# Tracksoar.net
KiCad netlist of a schematic drawn in EAGLE
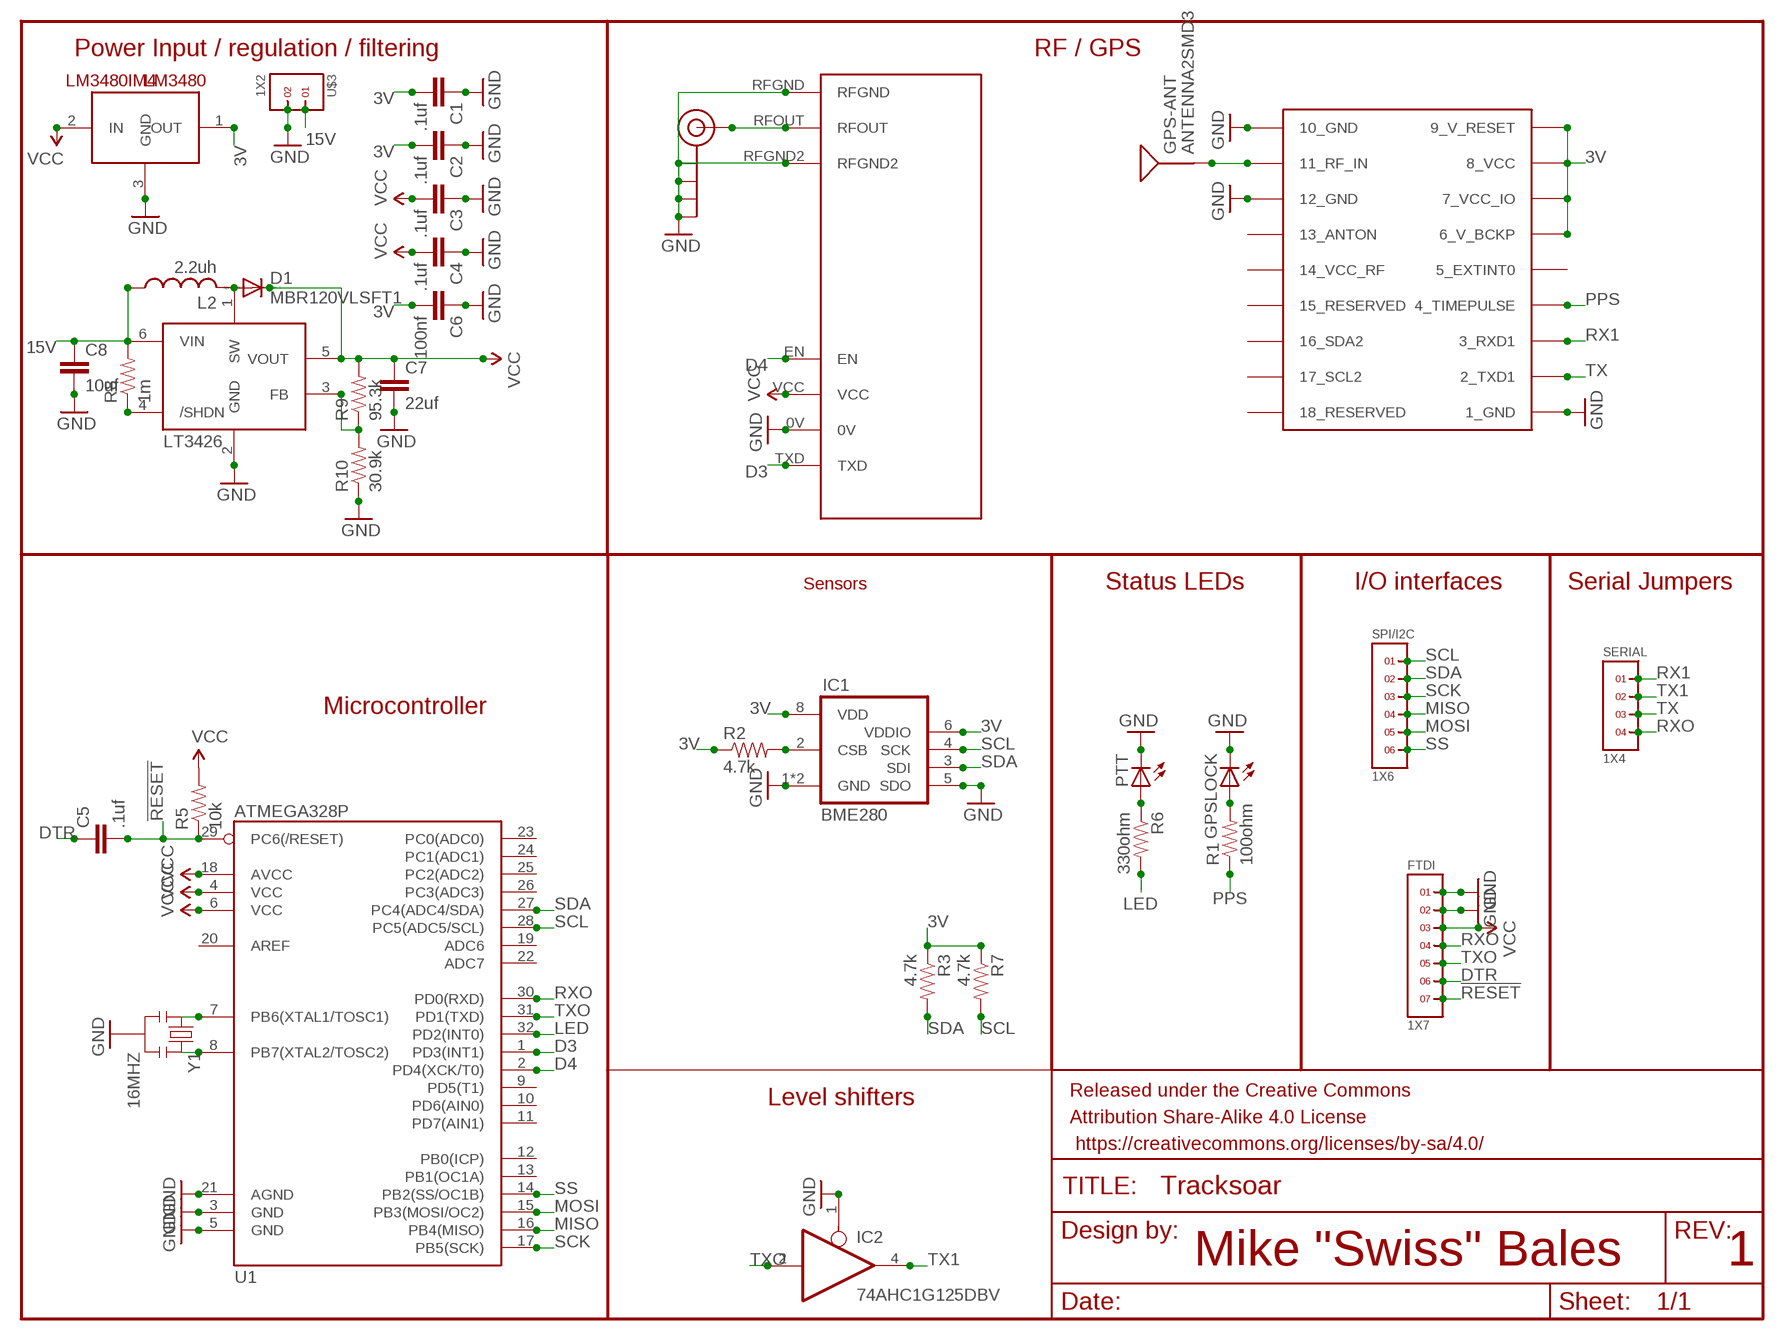
[diagram p0: schematic, sheet 1]

(export (version "E")
  (design (tool "Eeschema 10.0.6"))
  (components
    (comp (ref "C1")
      (value ".1uf")
      (footprint "eagle-import:0805")
      (libsource (lib "eagle-import") (part "CAP0805"))
    )
    (comp (ref "C2")
      (value ".1uf")
      (footprint "eagle-import:0805")
      (libsource (lib "eagle-import") (part "CAP0805"))
    )
    (comp (ref "C3")
      (value ".1uf")
      (footprint "eagle-import:0805")
      (libsource (lib "eagle-import") (part "CAP0805"))
    )
    (comp (ref "C4")
      (value ".1uf")
      (footprint "eagle-import:0805")
      (libsource (lib "eagle-import") (part "CAP0805"))
    )
    (comp (ref "C5")
      (value ".1uf")
      (footprint "eagle-import:0805")
      (libsource (lib "eagle-import") (part "CAP0805"))
    )
    (comp (ref "C6")
      (value "100nf")
      (footprint "eagle-import:0805")
      (libsource (lib "eagle-import") (part "CAP0805"))
    )
    (comp (ref "C7")
      (value "22uf")
      (footprint "eagle-import:0805")
      (libsource (lib "eagle-import") (part "CAP0805"))
    )
    (comp (ref "C8")
      (value "10uf")
      (footprint "eagle-import:0805")
      (libsource (lib "eagle-import") (part "CAP0805"))
    )
    (comp (ref "D1")
      (value "MBR120VLSFT1")
      (footprint "eagle-import:SOD123")
      (libsource (lib "eagle-import") (part "DIODE-SOD123"))
    )
    (comp (ref "FRAME1")
      (value "FRAME-LETTER")
      (footprint "eagle-import:CREATIVE_COMMONS")
      (libsource (lib "eagle-import") (part "FRAME-LETTER"))
    )
    (comp (ref "FTDI")
      (value "1X7")
      (footprint "eagle-import:1X7")
      (libsource (lib "eagle-import") (part "1X7"))
    )
    (comp (ref "GPS-ANT")
      (value "ANTENNA2SMD3")
      (footprint "eagle-import:ANTENNA-CHIP4")
      (libsource (lib "eagle-import") (part "ANTENNA2SMD3"))
    )
    (comp (ref "GPSLOCK")
      (value "LEDCHIP-LED0805")
      (footprint "eagle-import:CHIP-LED0805")
      (libsource (lib "eagle-import") (part "LEDCHIP-LED0805"))
    )
    (comp (ref "IC1")
      (value "BME280")
      (footprint "eagle-import:BME280")
      (libsource (lib "eagle-import") (part "BME280"))
    )
    (comp (ref "IC2")
      (value "74AHC1G125DBV")
      (footprint "eagle-import:SOT23-5")
      (libsource (lib "eagle-import") (part "741G125DBVAHC"))
    )
    (comp (ref "J$1")
      (value "SMA_EDGE")
      (footprint "eagle-import:SMA-EDGE")
      (libsource (lib "eagle-import") (part "SMA_EDGE"))
    )
    (comp (ref "L2")
      (value "2.2uh")
      (footprint "eagle-import:L1812")
      (libsource (lib "eagle-import") (part "L-USL1812"))
    )
    (comp (ref "LM3480")
      (value "LM3480IM4")
      (footprint "eagle-import:SOT23-3")
      (libsource (lib "eagle-import") (part "LM3480IM4"))
    )
    (comp (ref "LT3426")
      (value "LT3426")
      (footprint "eagle-import:SOT23-6")
      (libsource (lib "eagle-import") (part "LT3426"))
    )
    (comp (ref "PTT")
      (value "LEDCHIP-LED0805")
      (footprint "eagle-import:CHIP-LED0805")
      (libsource (lib "eagle-import") (part "LEDCHIP-LED0805"))
    )
    (comp (ref "R1")
      (value "100ohm")
      (footprint "eagle-import:0805")
      (libsource (lib "eagle-import") (part "RESISTOR0805-RES"))
    )
    (comp (ref "R2")
      (value "4.7k")
      (footprint "eagle-import:0805")
      (libsource (lib "eagle-import") (part "RESISTOR0805-RES"))
    )
    (comp (ref "R3")
      (value "4.7k")
      (footprint "eagle-import:0805")
      (libsource (lib "eagle-import") (part "RESISTOR0805-RES"))
    )
    (comp (ref "R5")
      (value "10k")
      (footprint "eagle-import:0805")
      (libsource (lib "eagle-import") (part "RESISTOR0805-RES"))
    )
    (comp (ref "R6")
      (value "330ohm")
      (footprint "eagle-import:0805")
      (libsource (lib "eagle-import") (part "RESISTOR0805-RES"))
    )
    (comp (ref "R7")
      (value "4.7k")
      (footprint "eagle-import:0805")
      (libsource (lib "eagle-import") (part "RESISTOR0805-RES"))
    )
    (comp (ref "R8")
      (value "1m")
      (footprint "eagle-import:0805")
      (libsource (lib "eagle-import") (part "RESISTOR0805-RES"))
    )
    (comp (ref "R9")
      (value "95.3k")
      (footprint "eagle-import:0805")
      (libsource (lib "eagle-import") (part "RESISTOR0805-RES"))
    )
    (comp (ref "R10")
      (value "30.9k")
      (footprint "eagle-import:0805")
      (libsource (lib "eagle-import") (part "RESISTOR0805-RES"))
    )
    (comp (ref "SERIAL")
      (value "1X4")
      (footprint "eagle-import:1X4")
      (libsource (lib "eagle-import") (part "1X4"))
    )
    (comp (ref "SPI/I2C")
      (value "1X6")
      (footprint "eagle-import:1X6")
      (libsource (lib "eagle-import") (part "1X6"))
    )
    (comp (ref "U$1")
      (value "UBLOX_MAX")
      (footprint "eagle-import:UBLOX_MAX")
      (libsource (lib "eagle-import") (part "UBLOX_MAX"))
    )
    (comp (ref "U$2")
      (value "RADIOMETRIX-HX1")
      (footprint "eagle-import:RADIOMETRIX-HX1")
      (libsource (lib "eagle-import") (part "RADIOMETRIX-HX1"))
    )
    (comp (ref "U$3")
      (value "1X2")
      (footprint "eagle-import:1X2")
      (libsource (lib "eagle-import") (part "1X2"))
    )
    (comp (ref "U1")
      (value "ATMEGA328P")
      (footprint "eagle-import:MLF32")
      (libsource (lib "eagle-import") (part "ATMEGA168MLF"))
    )
    (comp (ref "Y1")
      (value "16MHZ")
      (footprint "eagle-import:RESONATOR-SMD")
      (libsource (lib "eagle-import") (part "RESONATOR16MHZ"))
    )
  )
  (nets
    (net (code "1") (name "/3V") (class "Default")
      (node (ref "C1") (pin "2") (pinfunction "2_2") (pintype "passive"))
      (node (ref "C2") (pin "2") (pinfunction "2_2") (pintype "passive"))
      (node (ref "C6") (pin "2") (pinfunction "2_2") (pintype "passive"))
      (node (ref "IC1") (pin "6") (pinfunction "VDDIO_6") (pintype "power_in"))
      (node (ref "IC1") (pin "8") (pinfunction "VDD_8") (pintype "power_in"))
      (node (ref "LM3480") (pin "1") (pinfunction "OUT_1") (pintype "bidirectional"))
      (node (ref "R2") (pin "1") (pinfunction "1_1") (pintype "passive"))
      (node (ref "R3") (pin "1") (pinfunction "1_1") (pintype "passive"))
      (node (ref "R7") (pin "1") (pinfunction "1_1") (pintype "passive"))
      (node (ref "U$1") (pin "6_V_BCKP") (pinfunction "6_V_BCKP_6_V_BCKP") (pintype "bidirectional"))
      (node (ref "U$1") (pin "7_VCC_IO") (pinfunction "7_VCC_IO_7_VCC_IO") (pintype "power_in"))
      (node (ref "U$1") (pin "8_VCC") (pinfunction "8_VCC_8_VCC") (pintype "power_in"))
      (node (ref "U$1") (pin "9_V_RESET") (pinfunction "9_V_RESET_9_V_RESET") (pintype "power_in"))
    )
    (net (code "2") (name "/15V") (class "Default")
      (node (ref "C8") (pin "1") (pinfunction "1_1") (pintype "passive"))
      (node (ref "L2") (pin "1") (pinfunction "1_1") (pintype "passive"))
      (node (ref "LT3426") (pin "6") (pinfunction "VIN_6") (pintype "input"))
      (node (ref "R8") (pin "2") (pinfunction "2_2") (pintype "passive"))
      (node (ref "U$3") (pin "1") (pinfunction "1_1") (pintype "bidirectional"))
    )
    (net (code "3") (name "/D3") (class "Default")
      (node (ref "U$2") (pin "TXD") (pinfunction "TXD_TXD") (pintype "bidirectional"))
      (node (ref "U1") (pin "1") (pinfunction "PD3(INT1)_1") (pintype "bidirectional"))
    )
    (net (code "4") (name "/D4") (class "Default")
      (node (ref "U$2") (pin "EN") (pinfunction "EN_EN") (pintype "bidirectional"))
      (node (ref "U1") (pin "2") (pinfunction "PD4(XCK/T0)_2") (pintype "bidirectional"))
    )
    (net (code "5") (name "/DTR") (class "Default")
      (node (ref "C5") (pin "1") (pinfunction "1_1") (pintype "passive"))
      (node (ref "FTDI") (pin "6") (pinfunction "6_6") (pintype "bidirectional"))
    )
    (net (code "6") (name "/LED") (class "Default")
      (node (ref "R6") (pin "2") (pinfunction "2_2") (pintype "passive"))
      (node (ref "U1") (pin "32") (pinfunction "PD2(INT0)_32") (pintype "bidirectional"))
    )
    (net (code "7") (name "/MISO") (class "Default")
      (node (ref "SPI/I2C") (pin "4") (pinfunction "4_4") (pintype "bidirectional"))
      (node (ref "U1") (pin "16") (pinfunction "PB4(MISO)_16") (pintype "bidirectional"))
    )
    (net (code "8") (name "/MOSI") (class "Default")
      (node (ref "SPI/I2C") (pin "5") (pinfunction "5_5") (pintype "bidirectional"))
      (node (ref "U1") (pin "15") (pinfunction "PB3(MOSI/OC2)_15") (pintype "bidirectional"))
    )
    (net (code "9") (name "/PPS") (class "Default")
      (node (ref "R1") (pin "1") (pinfunction "1_1") (pintype "passive"))
      (node (ref "U$1") (pin "4_TIMEPULSE") (pinfunction "4_TIMEPULSE_4_TIMEPULSE") (pintype "bidirectional"))
    )
    (net (code "10") (name "/RX1") (class "Default")
      (node (ref "SERIAL") (pin "1") (pinfunction "1_1") (pintype "bidirectional"))
      (node (ref "U$1") (pin "3_RXD1") (pinfunction "3_RXD1_3_RXD1") (pintype "bidirectional"))
    )
    (net (code "11") (name "/RXO") (class "Default")
      (node (ref "FTDI") (pin "4") (pinfunction "4_4") (pintype "bidirectional"))
      (node (ref "SERIAL") (pin "4") (pinfunction "4_4") (pintype "bidirectional"))
      (node (ref "U1") (pin "30") (pinfunction "PD0(RXD)_30") (pintype "bidirectional"))
    )
    (net (code "12") (name "/SCK") (class "Default")
      (node (ref "SPI/I2C") (pin "3") (pinfunction "3_3") (pintype "bidirectional"))
      (node (ref "U1") (pin "17") (pinfunction "PB5(SCK)_17") (pintype "bidirectional"))
    )
    (net (code "13") (name "/SCL") (class "Default")
      (node (ref "IC1") (pin "4") (pinfunction "SCK_4") (pintype "bidirectional"))
      (node (ref "R7") (pin "2") (pinfunction "2_2") (pintype "passive"))
      (node (ref "SPI/I2C") (pin "1") (pinfunction "1_1") (pintype "bidirectional"))
      (node (ref "U1") (pin "28") (pinfunction "PC5(ADC5/SCL)_28") (pintype "bidirectional"))
    )
    (net (code "14") (name "/SDA") (class "Default")
      (node (ref "IC1") (pin "3") (pinfunction "SDI_3") (pintype "bidirectional"))
      (node (ref "R3") (pin "2") (pinfunction "2_2") (pintype "passive"))
      (node (ref "SPI/I2C") (pin "2") (pinfunction "2_2") (pintype "bidirectional"))
      (node (ref "U1") (pin "27") (pinfunction "PC4(ADC4/SDA)_27") (pintype "bidirectional"))
    )
    (net (code "15") (name "/SS") (class "Default")
      (node (ref "SPI/I2C") (pin "6") (pinfunction "6_6") (pintype "bidirectional"))
      (node (ref "U1") (pin "14") (pinfunction "PB2(SS/OC1B)_14") (pintype "bidirectional"))
    )
    (net (code "16") (name "/TX") (class "Default")
      (node (ref "SERIAL") (pin "3") (pinfunction "3_3") (pintype "bidirectional"))
      (node (ref "U$1") (pin "2_TXD1") (pinfunction "2_TXD1_2_TXD1") (pintype "bidirectional"))
    )
    (net (code "17") (name "/TX1") (class "Default")
      (node (ref "IC2") (pin "4") (pinfunction "O_4") (pintype "tri_state"))
      (node (ref "SERIAL") (pin "2") (pinfunction "2_2") (pintype "bidirectional"))
    )
    (net (code "18") (name "/TXO") (class "Default")
      (node (ref "FTDI") (pin "5") (pinfunction "5_5") (pintype "bidirectional"))
      (node (ref "IC2") (pin "2") (pinfunction "I_2") (pintype "input"))
      (node (ref "U1") (pin "31") (pinfunction "PD1(TXD)_31") (pintype "bidirectional"))
    )
    (net (code "19") (name "/~{RESET}") (class "Default")
      (node (ref "C5") (pin "2") (pinfunction "2_2") (pintype "passive"))
      (node (ref "FTDI") (pin "7") (pinfunction "7_7") (pintype "bidirectional"))
      (node (ref "R5") (pin "1") (pinfunction "1_1") (pintype "passive"))
      (node (ref "U1") (pin "29") (pinfunction "PC6(/RESET)_29") (pintype "bidirectional"))
    )
    (net (code "20") (name "GND") (class "Default")
      (node (ref "C1") (pin "1") (pinfunction "1_1") (pintype "passive"))
      (node (ref "C2") (pin "1") (pinfunction "1_1") (pintype "passive"))
      (node (ref "C3") (pin "1") (pinfunction "1_1") (pintype "passive"))
      (node (ref "C4") (pin "1") (pinfunction "1_1") (pintype "passive"))
      (node (ref "C6") (pin "1") (pinfunction "1_1") (pintype "passive"))
      (node (ref "C7") (pin "2") (pinfunction "2_2") (pintype "passive"))
      (node (ref "C8") (pin "2") (pinfunction "2_2") (pintype "passive"))
      (node (ref "FTDI") (pin "1") (pinfunction "1_1") (pintype "bidirectional"))
      (node (ref "FTDI") (pin "2") (pinfunction "2_2") (pintype "bidirectional"))
      (node (ref "GPSLOCK") (pin "C") (pinfunction "C_C") (pintype "passive"))
      (node (ref "IC1") (pin "1") (pinfunction "GND_1") (pintype "power_in"))
      (node (ref "IC1") (pin "5") (pinfunction "SDO_5") (pintype "input"))
      (node (ref "IC1") (pin "7") (pinfunction "GND_7") (pintype "power_in"))
      (node (ref "IC2") (pin "1") (pinfunction "OE_1") (pintype "input"))
      (node (ref "J$1") (pin "GND@0") (pinfunction "GND_GND@0") (pintype "bidirectional"))
      (node (ref "J$1") (pin "GND@1") (pinfunction "GND_GND@1") (pintype "bidirectional"))
      (node (ref "J$1") (pin "GND@2") (pinfunction "GND_GND@2") (pintype "bidirectional"))
      (node (ref "J$1") (pin "GND@3") (pinfunction "GND_GND@3") (pintype "bidirectional"))
      (node (ref "LM3480") (pin "3") (pinfunction "GND_3") (pintype "bidirectional"))
      (node (ref "LT3426") (pin "2") (pinfunction "GND_2") (pintype "power_in"))
      (node (ref "PTT") (pin "C") (pinfunction "C_C") (pintype "passive"))
      (node (ref "R10") (pin "1") (pinfunction "1_1") (pintype "passive"))
      (node (ref "U$1") (pin "10_GND") (pinfunction "10_GND_10_GND") (pintype "power_in"))
      (node (ref "U$1") (pin "12_GND") (pinfunction "12_GND_12_GND") (pintype "power_in"))
      (node (ref "U$1") (pin "1_GND") (pinfunction "1_GND_1_GND") (pintype "power_in"))
      (node (ref "U$2") (pin "0V") (pinfunction "0V_0V") (pintype "bidirectional"))
      (node (ref "U$2") (pin "RFGND") (pinfunction "RFGND_RFGND") (pintype "bidirectional"))
      (node (ref "U$2") (pin "RFGND2") (pinfunction "RFGND2_RFGND2") (pintype "bidirectional"))
      (node (ref "U$3") (pin "2") (pinfunction "2_2") (pintype "bidirectional"))
      (node (ref "U1") (pin "21") (pinfunction "AGND_21") (pintype "bidirectional"))
      (node (ref "U1") (pin "3") (pinfunction "GND_3") (pintype "bidirectional"))
      (node (ref "U1") (pin "5") (pinfunction "GND_5") (pintype "bidirectional"))
      (node (ref "Y1") (pin "2") (pinfunction "2_2") (pintype "passive"))
    )
    (net (code "21") (name "Net-(GPS-ANT-SIGNAL)") (class "Default")
      (node (ref "GPS-ANT") (pin "SIG") (pinfunction "SIGNAL_SIG") (pintype "bidirectional"))
      (node (ref "U$1") (pin "11_RF_IN") (pinfunction "11_RF_IN_11_RF_IN") (pintype "bidirectional"))
    )
    (net (code "22") (name "Net-(GPSLOCK-PadA)") (class "Default")
      (node (ref "GPSLOCK") (pin "A") (pinfunction "A_A") (pintype "passive"))
      (node (ref "R1") (pin "2") (pinfunction "2_2") (pintype "passive"))
    )
    (net (code "23") (name "Net-(IC1-CSB)") (class "Default")
      (node (ref "IC1") (pin "2") (pinfunction "CSB_2") (pintype "input"))
      (node (ref "R2") (pin "2") (pinfunction "2_2") (pintype "passive"))
    )
    (net (code "24") (name "Net-(J$1-SIGNAL)") (class "Default")
      (node (ref "J$1") (pin "SIG") (pinfunction "SIGNAL_SIG") (pintype "bidirectional"))
      (node (ref "U$2") (pin "RFOUT") (pinfunction "RFOUT_RFOUT") (pintype "bidirectional"))
    )
    (net (code "25") (name "Net-(LT3426-FB)") (class "Default")
      (node (ref "LT3426") (pin "3") (pinfunction "FB_3") (pintype "input"))
      (node (ref "R10") (pin "2") (pinfunction "2_2") (pintype "passive"))
      (node (ref "R9") (pin "1") (pinfunction "1_1") (pintype "passive"))
    )
    (net (code "26") (name "Net-(LT3426-SW)") (class "Default")
      (node (ref "D1") (pin "A") (pinfunction "A_A") (pintype "passive"))
      (node (ref "L2") (pin "2") (pinfunction "2_2") (pintype "passive"))
      (node (ref "LT3426") (pin "1") (pinfunction "SW_1") (pintype "output"))
    )
    (net (code "27") (name "Net-(LT3426-{slash}SHDN)") (class "Default")
      (node (ref "LT3426") (pin "4") (pinfunction "/SHDN_4") (pintype "input"))
      (node (ref "R8") (pin "1") (pinfunction "1_1") (pintype "passive"))
    )
    (net (code "28") (name "Net-(PTT-PadA)") (class "Default")
      (node (ref "PTT") (pin "A") (pinfunction "A_A") (pintype "passive"))
      (node (ref "R6") (pin "1") (pinfunction "1_1") (pintype "passive"))
    )
    (net (code "29") (name "Net-(U1-PB6(XTAL1{slash}TOSC1))") (class "Default")
      (node (ref "U1") (pin "7") (pinfunction "PB6(XTAL1/TOSC1)_7") (pintype "bidirectional"))
      (node (ref "Y1") (pin "1") (pinfunction "1_1") (pintype "passive"))
    )
    (net (code "30") (name "Net-(U1-PB7(XTAL2{slash}TOSC2))") (class "Default")
      (node (ref "U1") (pin "8") (pinfunction "PB7(XTAL2/TOSC2)_8") (pintype "bidirectional"))
      (node (ref "Y1") (pin "3") (pinfunction "3_3") (pintype "passive"))
    )
    (net (code "31") (name "VCC") (class "Default")
      (node (ref "C3") (pin "2") (pinfunction "2_2") (pintype "passive"))
      (node (ref "C4") (pin "2") (pinfunction "2_2") (pintype "passive"))
      (node (ref "C7") (pin "1") (pinfunction "1_1") (pintype "passive"))
      (node (ref "D1") (pin "C") (pinfunction "C_C") (pintype "passive"))
      (node (ref "FTDI") (pin "3") (pinfunction "3_3") (pintype "bidirectional"))
      (node (ref "LM3480") (pin "2") (pinfunction "IN_2") (pintype "bidirectional"))
      (node (ref "LT3426") (pin "5") (pinfunction "VOUT_5") (pintype "output"))
      (node (ref "R5") (pin "2") (pinfunction "2_2") (pintype "passive"))
      (node (ref "R9") (pin "2") (pinfunction "2_2") (pintype "passive"))
      (node (ref "U$2") (pin "VCC") (pinfunction "VCC_VCC") (pintype "bidirectional"))
      (node (ref "U1") (pin "18") (pinfunction "AVCC_18") (pintype "bidirectional"))
      (node (ref "U1") (pin "4") (pinfunction "VCC_4") (pintype "bidirectional"))
      (node (ref "U1") (pin "6") (pinfunction "VCC_6") (pintype "bidirectional"))
    )
    (net (code "32") (name "unconnected-(U$1-Pad5_EXTINT0)") (class "Default")
      (node (ref "U$1") (pin "5_EXTINT0") (pinfunction "5_EXTINT0_5_EXTINT0") (pintype "bidirectional"))
    )
    (net (code "33") (name "unconnected-(U$1-Pad13_ANTON)") (class "Default")
      (node (ref "U$1") (pin "13_ANTON") (pinfunction "13_ANTON_13_ANTON") (pintype "bidirectional"))
    )
    (net (code "34") (name "unconnected-(U$1-Pad14_VCC_RF)") (class "Default")
      (node (ref "U$1") (pin "14_VCC_RF") (pinfunction "14_VCC_RF_14_VCC_RF") (pintype "bidirectional"))
    )
    (net (code "35") (name "unconnected-(U$1-Pad15_RESERVED)") (class "Default")
      (node (ref "U$1") (pin "15_RESERVED") (pinfunction "15_RESERVED_15_RESERVED") (pintype "bidirectional"))
    )
    (net (code "36") (name "unconnected-(U$1-Pad16_SDA2)") (class "Default")
      (node (ref "U$1") (pin "16_SDA2") (pinfunction "16_SDA2_16_SDA2") (pintype "bidirectional"))
    )
    (net (code "37") (name "unconnected-(U$1-Pad17_SCL2)") (class "Default")
      (node (ref "U$1") (pin "17_SCL2") (pinfunction "17_SCL2_17_SCL2") (pintype "bidirectional"))
    )
    (net (code "38") (name "unconnected-(U$1-Pad18_RESERVED)") (class "Default")
      (node (ref "U$1") (pin "18_RESERVED") (pinfunction "18_RESERVED_18_RESERVED") (pintype "bidirectional"))
    )
    (net (code "39") (name "unconnected-(U1-ADC6-Pad19)") (class "Default")
      (node (ref "U1") (pin "19") (pinfunction "ADC6_19") (pintype "bidirectional"))
    )
    (net (code "40") (name "unconnected-(U1-ADC7-Pad22)") (class "Default")
      (node (ref "U1") (pin "22") (pinfunction "ADC7_22") (pintype "bidirectional"))
    )
    (net (code "41") (name "unconnected-(U1-AREF-Pad20)") (class "Default")
      (node (ref "U1") (pin "20") (pinfunction "AREF_20") (pintype "bidirectional"))
    )
    (net (code "42") (name "unconnected-(U1-PB0(ICP)-Pad12)") (class "Default")
      (node (ref "U1") (pin "12") (pinfunction "PB0(ICP)_12") (pintype "bidirectional"))
    )
    (net (code "43") (name "unconnected-(U1-PB1(OC1A)-Pad13)") (class "Default")
      (node (ref "U1") (pin "13") (pinfunction "PB1(OC1A)_13") (pintype "bidirectional"))
    )
    (net (code "44") (name "unconnected-(U1-PC0(ADC0)-Pad23)") (class "Default")
      (node (ref "U1") (pin "23") (pinfunction "PC0(ADC0)_23") (pintype "bidirectional"))
    )
    (net (code "45") (name "unconnected-(U1-PC1(ADC1)-Pad24)") (class "Default")
      (node (ref "U1") (pin "24") (pinfunction "PC1(ADC1)_24") (pintype "bidirectional"))
    )
    (net (code "46") (name "unconnected-(U1-PC2(ADC2)-Pad25)") (class "Default")
      (node (ref "U1") (pin "25") (pinfunction "PC2(ADC2)_25") (pintype "bidirectional"))
    )
    (net (code "47") (name "unconnected-(U1-PC3(ADC3)-Pad26)") (class "Default")
      (node (ref "U1") (pin "26") (pinfunction "PC3(ADC3)_26") (pintype "bidirectional"))
    )
    (net (code "48") (name "unconnected-(U1-PD5(T1)-Pad9)") (class "Default")
      (node (ref "U1") (pin "9") (pinfunction "PD5(T1)_9") (pintype "bidirectional"))
    )
    (net (code "49") (name "unconnected-(U1-PD6(AIN0)-Pad10)") (class "Default")
      (node (ref "U1") (pin "10") (pinfunction "PD6(AIN0)_10") (pintype "bidirectional"))
    )
    (net (code "50") (name "unconnected-(U1-PD7(AIN1)-Pad11)") (class "Default")
      (node (ref "U1") (pin "11") (pinfunction "PD7(AIN1)_11") (pintype "bidirectional"))
    )
  )
)
